# SYZYGY_IO_PORTS.net
KiCad netlist of a schematic drawn in Altium Designer
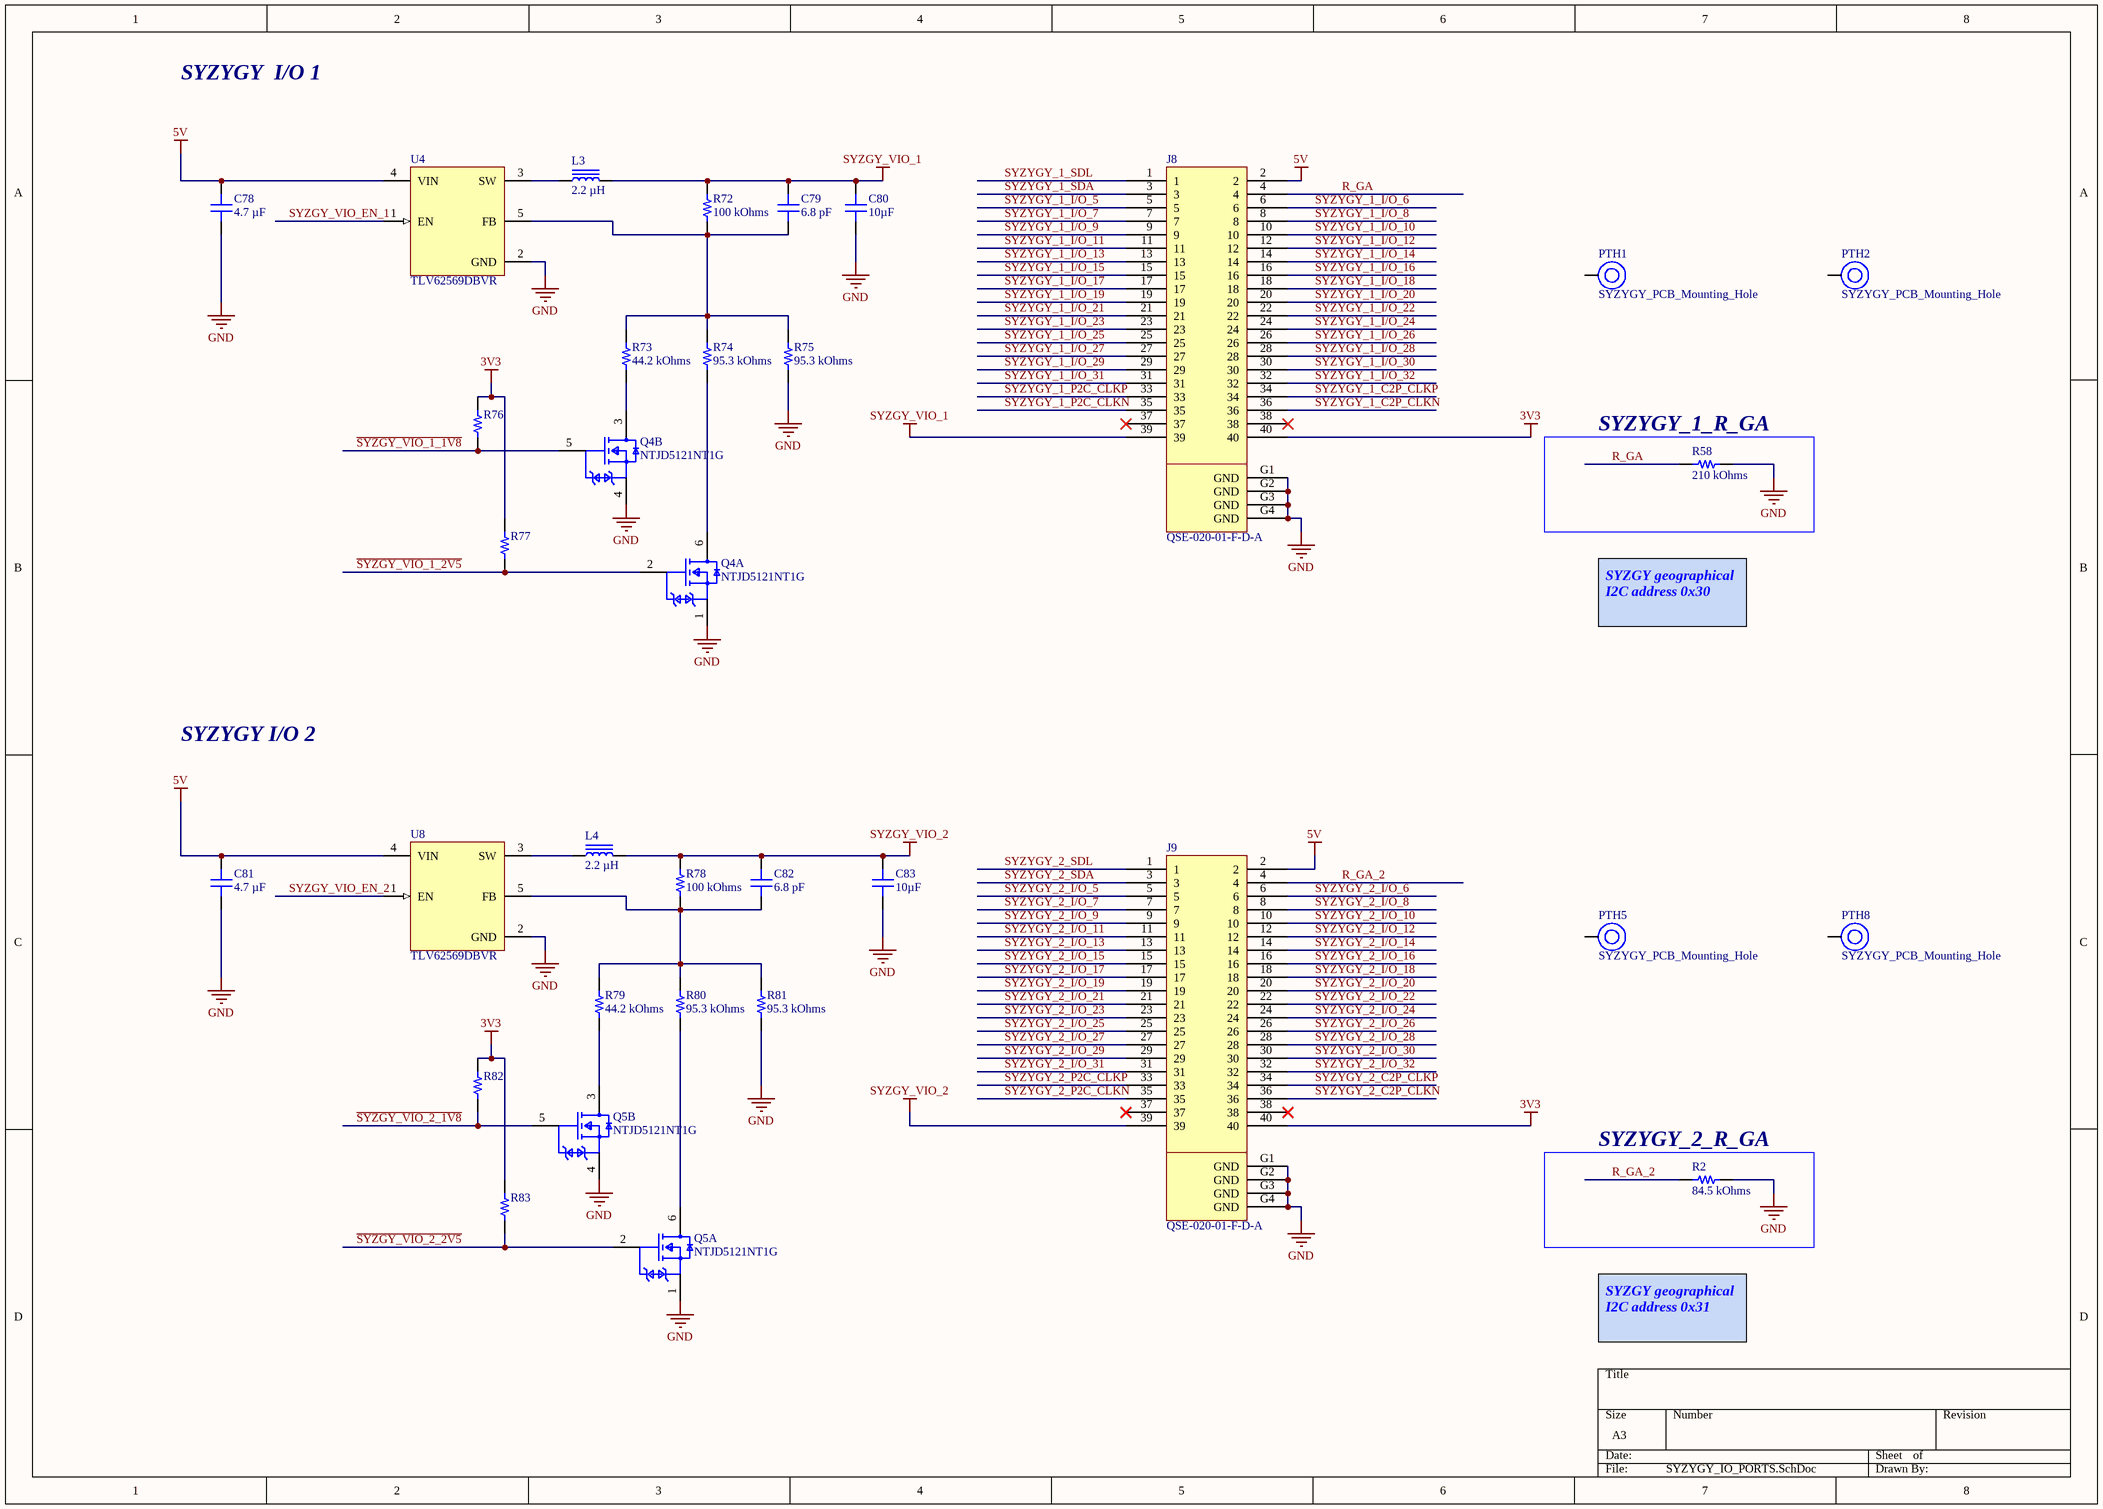
[diagram p0: SYZYGY_IO_PORTS.SchDoc]

(export (version "E")
  (design (tool "Eeschema 10.0.6"))
  (components
    (comp (ref "C78")
      (value "4.7 µF")
      (footprint "CAP 0805_2012")
      (description "CAP CER 4.7UF 25V X7R 0805")
      (fields
        (field (name "PART NUMBER") "CL21B475KAFNNNE")
        (field (name "MANUFACTURER") "Samsung Electro-Mechanics")
      )
      (libsource (lib "Celestial Altium Library - altium_library") (part "Capacitor"))
    )
    (comp (ref "C79")
      (value "6.8 pF")
      (footprint "CAP 0402_1005")
      (description "CAP CER 6.8PF 16V C0G/NP0 0402")
      (fields (field (name "PART NUMBER") "885012005024") (field (name "MANUFACTURER") "Würth Elektronik"))
      (libsource (lib "Celestial Altium Library - altium_library") (part "Capacitor"))
    )
    (comp (ref "C80")
      (value "10µF")
      (footprint "CAP 0805_2012")
      (description "CAP CER 10UF 10V X7R 0805")
      (fields (field (name "PART NUMBER") "0805ZC106MAT2A") (field (name "MANUFACTURER") "AVX Corporation"))
      (libsource (lib "Celestial Altium Library - altium_library") (part "Capacitor"))
    )
    (comp (ref "C81")
      (value "4.7 µF")
      (footprint "CAP 0805_2012")
      (description "CAP CER 4.7UF 25V X7R 0805")
      (fields
        (field (name "PART NUMBER") "CL21B475KAFNNNE")
        (field (name "MANUFACTURER") "Samsung Electro-Mechanics")
      )
      (libsource (lib "Celestial Altium Library - altium_library") (part "Capacitor"))
    )
    (comp (ref "C82")
      (value "6.8 pF")
      (footprint "CAP 0402_1005")
      (description "CAP CER 6.8PF 16V C0G/NP0 0402")
      (fields (field (name "PART NUMBER") "885012005024") (field (name "MANUFACTURER") "Würth Elektronik"))
      (libsource (lib "Celestial Altium Library - altium_library") (part "Capacitor"))
    )
    (comp (ref "C83")
      (value "10µF")
      (footprint "CAP 0805_2012")
      (description "CAP CER 10UF 10V X7R 0805")
      (fields (field (name "PART NUMBER") "0805ZC106MAT2A") (field (name "MANUFACTURER") "AVX Corporation"))
      (libsource (lib "Celestial Altium Library - altium_library") (part "Capacitor"))
    )
    (comp (ref "J8")
      (value "QSE-020-01-F-D-A")
      (footprint "Components - 26.11.22 - 19.48:QSE-020-01-F-D-A-Footprint-1")
      (description "Conn High Speed Socket Strip SKT 40 POS 0.8mm Solder ST SMD Tray")
      (libsource (lib "Components - 26.11.22 - 19.48") (part "CMP-002-00073-2"))
    )
    (comp (ref "J9")
      (value "QSE-020-01-F-D-A")
      (footprint "Components - 26.11.22 - 19.48:QSE-020-01-F-D-A-Footprint-1")
      (description "Conn High Speed Socket Strip SKT 40 POS 0.8mm Solder ST SMD Tray")
      (libsource (lib "Components - 26.11.22 - 19.48") (part "CMP-002-00073-2"))
    )
    (comp (ref "L3")
      (value "2.2 µH")
      (footprint "TDK VLS252010HBX-1")
      (description "FIXED IND 2.2UH 1.76A 120MOHM SM")
      (fields
        (field (name "PART NUMBER") "VLS252010HBX-2R2M-1")
        (field (name "MANUFACTURER") "TDK Corporation")
      )
      (libsource (lib "Celestial Altium Library - altium_library") (part "Inductor"))
    )
    (comp (ref "L4")
      (value "2.2 µH")
      (footprint "TDK VLS252010HBX-1")
      (description "FIXED IND 2.2UH 1.76A 120MOHM SM")
      (fields
        (field (name "PART NUMBER") "VLS252010HBX-2R2M-1")
        (field (name "MANUFACTURER") "TDK Corporation")
      )
      (libsource (lib "Celestial Altium Library - altium_library") (part "Inductor"))
    )
    (comp (ref "PTH1")
      (value "SYZYGY_PCB_Mounting_Hole")
      (footprint "SYZYGY_PCB_Mounting_Hole")
      (libsource (lib "T8_devkit_PCB") (part "SYZYGY_PCB_Mounting_Hole"))
    )
    (comp (ref "PTH2")
      (value "SYZYGY_PCB_Mounting_Hole")
      (footprint "SYZYGY_PCB_Mounting_Hole")
      (libsource (lib "T8_devkit_PCB") (part "SYZYGY_PCB_Mounting_Hole"))
    )
    (comp (ref "PTH5")
      (value "SYZYGY_PCB_Mounting_Hole")
      (footprint "SYZYGY_PCB_Mounting_Hole")
      (libsource (lib "T8_devkit_PCB") (part "SYZYGY_PCB_Mounting_Hole"))
    )
    (comp (ref "PTH8")
      (value "SYZYGY_PCB_Mounting_Hole")
      (footprint "SYZYGY_PCB_Mounting_Hole")
      (libsource (lib "T8_devkit_PCB") (part "SYZYGY_PCB_Mounting_Hole"))
    )
    (comp (ref "Q4")
      (value "NTJD5121NT1G")
      (footprint "FP-419B-02-MFG")
      (description "MOSFET 2N-CH 60V 0.295A SOT363")
      (libsource (lib "Components - 26.11.22 - 19.04") (part "CMP-013-00036-1"))
    )
    (comp (ref "Q5")
      (value "NTJD5121NT1G")
      (footprint "FP-419B-02-MFG")
      (description "MOSFET 2N-CH 60V 0.295A SOT363")
      (libsource (lib "Components - 26.11.22 - 19.04") (part "CMP-013-00036-1"))
    )
    (comp (ref "R2")
      (value "84.5 kOhms")
      (footprint "RES 0402_1005")
      (description "RES 84.5K OHM 1% 1/16W 0402")
      (fields (field (name "PART NUMBER") "RC0402FR-0784K5L") (field (name "MANUFACTURER") "Yageo"))
      (libsource (lib "Celestial Altium Library - altium_library") (part "Resistor"))
    )
    (comp (ref "R58")
      (value "210 kOhms")
      (footprint "RES 0402_1005")
      (description "RES 210K OHM 1% 1/16W 0402")
      (fields (field (name "PART NUMBER") "RC0402FR-07210KL") (field (name "MANUFACTURER") "Yageo"))
      (libsource (lib "Celestial Altium Library - altium_library") (part "Resistor"))
    )
    (comp (ref "R72")
      (value "100 kOhms")
      (footprint "RES 0402_1005")
      (description "RES SMD 100K OHM 1% 1/16W 0402")
      (fields (field (name "PART NUMBER") "AC0402FR-07100KL") (field (name "MANUFACTURER") "Yageo"))
      (libsource (lib "Celestial Altium Library - altium_library") (part "Resistor"))
    )
    (comp (ref "R73")
      (value "44.2 kOhms")
      (footprint "RES 0402_1005")
      (description "RES 44.2K OHM 1% 1/16W 0402")
      (fields (field (name "PART NUMBER") "RC0402FR-0744K2L") (field (name "MANUFACTURER") "Yageo"))
      (libsource (lib "Celestial Altium Library - altium_library") (part "Resistor"))
    )
    (comp (ref "R74")
      (value "95.3 kOhms")
      (footprint "RES 0402_1005")
      (description "RES 95.3K OHM 1% 1/16W 0402")
      (fields (field (name "PART NUMBER") "RC0402FR-0795K3L") (field (name "MANUFACTURER") "Yageo"))
      (libsource (lib "Celestial Altium Library - altium_library") (part "Resistor"))
    )
    (comp (ref "R75")
      (value "95.3 kOhms")
      (footprint "RES 0402_1005")
      (description "RES 95.3K OHM 1% 1/16W 0402")
      (fields (field (name "PART NUMBER") "RC0402FR-0795K3L") (field (name "MANUFACTURER") "Yageo"))
      (libsource (lib "Celestial Altium Library - altium_library") (part "Resistor"))
    )
    (comp (ref "R76")
      (value "10 kOhms")
      (footprint "RES 0201_0603")
      (description "RES 10K OHM 1% 1/20W 0201")
      (fields (field (name "PART NUMBER") "RC0201FR-0710KL") (field (name "MANUFACTURER") "Yageo"))
      (libsource (lib "Celestial Altium Library - altium_library") (part "Resistor"))
    )
    (comp (ref "R77")
      (value "10 kOhms")
      (footprint "RES 0201_0603")
      (description "RES 10K OHM 1% 1/20W 0201")
      (fields (field (name "PART NUMBER") "RC0201FR-0710KL") (field (name "MANUFACTURER") "Yageo"))
      (libsource (lib "Celestial Altium Library - altium_library") (part "Resistor"))
    )
    (comp (ref "R78")
      (value "100 kOhms")
      (footprint "RES 0402_1005")
      (description "RES SMD 100K OHM 1% 1/16W 0402")
      (fields (field (name "PART NUMBER") "AC0402FR-07100KL") (field (name "MANUFACTURER") "Yageo"))
      (libsource (lib "Celestial Altium Library - altium_library") (part "Resistor"))
    )
    (comp (ref "R79")
      (value "44.2 kOhms")
      (footprint "RES 0402_1005")
      (description "RES 44.2K OHM 1% 1/16W 0402")
      (fields (field (name "PART NUMBER") "RC0402FR-0744K2L") (field (name "MANUFACTURER") "Yageo"))
      (libsource (lib "Celestial Altium Library - altium_library") (part "Resistor"))
    )
    (comp (ref "R80")
      (value "95.3 kOhms")
      (footprint "RES 0402_1005")
      (description "RES 95.3K OHM 1% 1/16W 0402")
      (fields (field (name "PART NUMBER") "RC0402FR-0795K3L") (field (name "MANUFACTURER") "Yageo"))
      (libsource (lib "Celestial Altium Library - altium_library") (part "Resistor"))
    )
    (comp (ref "R81")
      (value "95.3 kOhms")
      (footprint "RES 0402_1005")
      (description "RES 95.3K OHM 1% 1/16W 0402")
      (fields (field (name "PART NUMBER") "RC0402FR-0795K3L") (field (name "MANUFACTURER") "Yageo"))
      (libsource (lib "Celestial Altium Library - altium_library") (part "Resistor"))
    )
    (comp (ref "R82")
      (value "10 kOhms")
      (footprint "RES 0201_0603")
      (description "RES 10K OHM 1% 1/20W 0201")
      (fields (field (name "PART NUMBER") "RC0201FR-0710KL") (field (name "MANUFACTURER") "Yageo"))
      (libsource (lib "Celestial Altium Library - altium_library") (part "Resistor"))
    )
    (comp (ref "R83")
      (value "10 kOhms")
      (footprint "RES 0201_0603")
      (description "RES 10K OHM 1% 1/20W 0201")
      (fields (field (name "PART NUMBER") "RC0201FR-0710KL") (field (name "MANUFACTURER") "Yageo"))
      (libsource (lib "Celestial Altium Library - altium_library") (part "Resistor"))
    )
    (comp (ref "U4")
      (value "TLV62569DBVR")
      (footprint "FP-DBV0005A-IPC_C")
      (description "Conv DC-DC 2.5V to 5.5V Synchronous Step Down Single-Out 0.6V to 5.5V 2A 5-Pin SOT-23 T/R")
      (libsource (lib "Components - 26.11.22 - 18.56") (part "CMP-019-00054-4"))
    )
    (comp (ref "U8")
      (value "TLV62569DBVR")
      (footprint "FP-DBV0005A-IPC_C")
      (description "Conv DC-DC 2.5V to 5.5V Synchronous Step Down Single-Out 0.6V to 5.5V 2A 5-Pin SOT-23 T/R")
      (libsource (lib "Components - 26.11.22 - 18.56") (part "CMP-019-00054-4"))
    )
  )
  (nets
    (net (code "1") (name "/R_GA") (class "Default")
      (node (ref "J8") (pin "4") (pinfunction "4_4") (pintype "passive"))
      (node (ref "R58") (pin "1") (pinfunction "1_1") (pintype "passive"))
    )
    (net (code "2") (name "/R_GA_2") (class "Default")
      (node (ref "J9") (pin "4") (pinfunction "4_4") (pintype "passive"))
      (node (ref "R2") (pin "1") (pinfunction "1_1") (pintype "passive"))
    )
    (net (code "3") (name "/SYZGY_VIO_EN_1") (class "Default")
      (node (ref "U4") (pin "1") (pinfunction "EN_1") (pintype "input"))
    )
    (net (code "4") (name "/SYZGY_VIO_EN_2") (class "Default")
      (node (ref "U8") (pin "1") (pinfunction "EN_1") (pintype "input"))
    )
    (net (code "5") (name "/SYZYGY_1_C2P_CLKN") (class "Default")
      (node (ref "J8") (pin "36") (pinfunction "36_36") (pintype "passive"))
    )
    (net (code "6") (name "/SYZYGY_1_C2P_CLKP") (class "Default")
      (node (ref "J8") (pin "34") (pinfunction "34_34") (pintype "passive"))
    )
    (net (code "7") (name "/SYZYGY_1_I{slash}O_5") (class "Default")
      (node (ref "J8") (pin "5") (pinfunction "5_5") (pintype "passive"))
    )
    (net (code "8") (name "/SYZYGY_1_I{slash}O_6") (class "Default")
      (node (ref "J8") (pin "6") (pinfunction "6_6") (pintype "passive"))
    )
    (net (code "9") (name "/SYZYGY_1_I{slash}O_7") (class "Default")
      (node (ref "J8") (pin "7") (pinfunction "7_7") (pintype "passive"))
    )
    (net (code "10") (name "/SYZYGY_1_I{slash}O_8") (class "Default")
      (node (ref "J8") (pin "8") (pinfunction "8_8") (pintype "passive"))
    )
    (net (code "11") (name "/SYZYGY_1_I{slash}O_9") (class "Default")
      (node (ref "J8") (pin "9") (pinfunction "9_9") (pintype "passive"))
    )
    (net (code "12") (name "/SYZYGY_1_I{slash}O_10") (class "Default")
      (node (ref "J8") (pin "10") (pinfunction "10_10") (pintype "passive"))
    )
    (net (code "13") (name "/SYZYGY_1_I{slash}O_11") (class "Default")
      (node (ref "J8") (pin "11") (pinfunction "11_11") (pintype "passive"))
    )
    (net (code "14") (name "/SYZYGY_1_I{slash}O_12") (class "Default")
      (node (ref "J8") (pin "12") (pinfunction "12_12") (pintype "passive"))
    )
    (net (code "15") (name "/SYZYGY_1_I{slash}O_13") (class "Default")
      (node (ref "J8") (pin "13") (pinfunction "13_13") (pintype "passive"))
    )
    (net (code "16") (name "/SYZYGY_1_I{slash}O_14") (class "Default")
      (node (ref "J8") (pin "14") (pinfunction "14_14") (pintype "passive"))
    )
    (net (code "17") (name "/SYZYGY_1_I{slash}O_15") (class "Default")
      (node (ref "J8") (pin "15") (pinfunction "15_15") (pintype "passive"))
    )
    (net (code "18") (name "/SYZYGY_1_I{slash}O_16") (class "Default")
      (node (ref "J8") (pin "16") (pinfunction "16_16") (pintype "passive"))
    )
    (net (code "19") (name "/SYZYGY_1_I{slash}O_17") (class "Default")
      (node (ref "J8") (pin "17") (pinfunction "17_17") (pintype "passive"))
    )
    (net (code "20") (name "/SYZYGY_1_I{slash}O_18") (class "Default")
      (node (ref "J8") (pin "18") (pinfunction "18_18") (pintype "passive"))
    )
    (net (code "21") (name "/SYZYGY_1_I{slash}O_19") (class "Default")
      (node (ref "J8") (pin "19") (pinfunction "19_19") (pintype "passive"))
    )
    (net (code "22") (name "/SYZYGY_1_I{slash}O_20") (class "Default")
      (node (ref "J8") (pin "20") (pinfunction "20_20") (pintype "passive"))
    )
    (net (code "23") (name "/SYZYGY_1_I{slash}O_21") (class "Default")
      (node (ref "J8") (pin "21") (pinfunction "21_21") (pintype "passive"))
    )
    (net (code "24") (name "/SYZYGY_1_I{slash}O_22") (class "Default")
      (node (ref "J8") (pin "22") (pinfunction "22_22") (pintype "passive"))
    )
    (net (code "25") (name "/SYZYGY_1_I{slash}O_23") (class "Default")
      (node (ref "J8") (pin "23") (pinfunction "23_23") (pintype "passive"))
    )
    (net (code "26") (name "/SYZYGY_1_I{slash}O_24") (class "Default")
      (node (ref "J8") (pin "24") (pinfunction "24_24") (pintype "passive"))
    )
    (net (code "27") (name "/SYZYGY_1_I{slash}O_25") (class "Default")
      (node (ref "J8") (pin "25") (pinfunction "25_25") (pintype "passive"))
    )
    (net (code "28") (name "/SYZYGY_1_I{slash}O_26") (class "Default")
      (node (ref "J8") (pin "26") (pinfunction "26_26") (pintype "passive"))
    )
    (net (code "29") (name "/SYZYGY_1_I{slash}O_27") (class "Default")
      (node (ref "J8") (pin "27") (pinfunction "27_27") (pintype "passive"))
    )
    (net (code "30") (name "/SYZYGY_1_I{slash}O_28") (class "Default")
      (node (ref "J8") (pin "28") (pinfunction "28_28") (pintype "passive"))
    )
    (net (code "31") (name "/SYZYGY_1_I{slash}O_29") (class "Default")
      (node (ref "J8") (pin "29") (pinfunction "29_29") (pintype "passive"))
    )
    (net (code "32") (name "/SYZYGY_1_I{slash}O_30") (class "Default")
      (node (ref "J8") (pin "30") (pinfunction "30_30") (pintype "passive"))
    )
    (net (code "33") (name "/SYZYGY_1_I{slash}O_31") (class "Default")
      (node (ref "J8") (pin "31") (pinfunction "31_31") (pintype "passive"))
    )
    (net (code "34") (name "/SYZYGY_1_I{slash}O_32") (class "Default")
      (node (ref "J8") (pin "32") (pinfunction "32_32") (pintype "passive"))
    )
    (net (code "35") (name "/SYZYGY_1_P2C_CLKN") (class "Default")
      (node (ref "J8") (pin "35") (pinfunction "35_35") (pintype "passive"))
    )
    (net (code "36") (name "/SYZYGY_1_P2C_CLKP") (class "Default")
      (node (ref "J8") (pin "33") (pinfunction "33_33") (pintype "passive"))
    )
    (net (code "37") (name "/SYZYGY_1_SDA") (class "Default")
      (node (ref "J8") (pin "3") (pinfunction "3_3") (pintype "passive"))
    )
    (net (code "38") (name "/SYZYGY_1_SDL") (class "Default")
      (node (ref "J8") (pin "1") (pinfunction "1_1") (pintype "passive"))
    )
    (net (code "39") (name "/SYZYGY_2_C2P_CLKN") (class "Default")
      (node (ref "J9") (pin "36") (pinfunction "36_36") (pintype "passive"))
    )
    (net (code "40") (name "/SYZYGY_2_C2P_CLKP") (class "Default")
      (node (ref "J9") (pin "34") (pinfunction "34_34") (pintype "passive"))
    )
    (net (code "41") (name "/SYZYGY_2_I{slash}O_5") (class "Default")
      (node (ref "J9") (pin "5") (pinfunction "5_5") (pintype "passive"))
    )
    (net (code "42") (name "/SYZYGY_2_I{slash}O_6") (class "Default")
      (node (ref "J9") (pin "6") (pinfunction "6_6") (pintype "passive"))
    )
    (net (code "43") (name "/SYZYGY_2_I{slash}O_7") (class "Default")
      (node (ref "J9") (pin "7") (pinfunction "7_7") (pintype "passive"))
    )
    (net (code "44") (name "/SYZYGY_2_I{slash}O_8") (class "Default")
      (node (ref "J9") (pin "8") (pinfunction "8_8") (pintype "passive"))
    )
    (net (code "45") (name "/SYZYGY_2_I{slash}O_9") (class "Default")
      (node (ref "J9") (pin "9") (pinfunction "9_9") (pintype "passive"))
    )
    (net (code "46") (name "/SYZYGY_2_I{slash}O_10") (class "Default")
      (node (ref "J9") (pin "10") (pinfunction "10_10") (pintype "passive"))
    )
    (net (code "47") (name "/SYZYGY_2_I{slash}O_11") (class "Default")
      (node (ref "J9") (pin "11") (pinfunction "11_11") (pintype "passive"))
    )
    (net (code "48") (name "/SYZYGY_2_I{slash}O_12") (class "Default")
      (node (ref "J9") (pin "12") (pinfunction "12_12") (pintype "passive"))
    )
    (net (code "49") (name "/SYZYGY_2_I{slash}O_13") (class "Default")
      (node (ref "J9") (pin "13") (pinfunction "13_13") (pintype "passive"))
    )
    (net (code "50") (name "/SYZYGY_2_I{slash}O_14") (class "Default")
      (node (ref "J9") (pin "14") (pinfunction "14_14") (pintype "passive"))
    )
    (net (code "51") (name "/SYZYGY_2_I{slash}O_15") (class "Default")
      (node (ref "J9") (pin "15") (pinfunction "15_15") (pintype "passive"))
    )
    (net (code "52") (name "/SYZYGY_2_I{slash}O_16") (class "Default")
      (node (ref "J9") (pin "16") (pinfunction "16_16") (pintype "passive"))
    )
    (net (code "53") (name "/SYZYGY_2_I{slash}O_17") (class "Default")
      (node (ref "J9") (pin "17") (pinfunction "17_17") (pintype "passive"))
    )
    (net (code "54") (name "/SYZYGY_2_I{slash}O_18") (class "Default")
      (node (ref "J9") (pin "18") (pinfunction "18_18") (pintype "passive"))
    )
    (net (code "55") (name "/SYZYGY_2_I{slash}O_19") (class "Default")
      (node (ref "J9") (pin "19") (pinfunction "19_19") (pintype "passive"))
    )
    (net (code "56") (name "/SYZYGY_2_I{slash}O_20") (class "Default")
      (node (ref "J9") (pin "20") (pinfunction "20_20") (pintype "passive"))
    )
    (net (code "57") (name "/SYZYGY_2_I{slash}O_21") (class "Default")
      (node (ref "J9") (pin "21") (pinfunction "21_21") (pintype "passive"))
    )
    (net (code "58") (name "/SYZYGY_2_I{slash}O_22") (class "Default")
      (node (ref "J9") (pin "22") (pinfunction "22_22") (pintype "passive"))
    )
    (net (code "59") (name "/SYZYGY_2_I{slash}O_23") (class "Default")
      (node (ref "J9") (pin "23") (pinfunction "23_23") (pintype "passive"))
    )
    (net (code "60") (name "/SYZYGY_2_I{slash}O_24") (class "Default")
      (node (ref "J9") (pin "24") (pinfunction "24_24") (pintype "passive"))
    )
    (net (code "61") (name "/SYZYGY_2_I{slash}O_25") (class "Default")
      (node (ref "J9") (pin "25") (pinfunction "25_25") (pintype "passive"))
    )
    (net (code "62") (name "/SYZYGY_2_I{slash}O_26") (class "Default")
      (node (ref "J9") (pin "26") (pinfunction "26_26") (pintype "passive"))
    )
    (net (code "63") (name "/SYZYGY_2_I{slash}O_27") (class "Default")
      (node (ref "J9") (pin "27") (pinfunction "27_27") (pintype "passive"))
    )
    (net (code "64") (name "/SYZYGY_2_I{slash}O_28") (class "Default")
      (node (ref "J9") (pin "28") (pinfunction "28_28") (pintype "passive"))
    )
    (net (code "65") (name "/SYZYGY_2_I{slash}O_29") (class "Default")
      (node (ref "J9") (pin "29") (pinfunction "29_29") (pintype "passive"))
    )
    (net (code "66") (name "/SYZYGY_2_I{slash}O_30") (class "Default")
      (node (ref "J9") (pin "30") (pinfunction "30_30") (pintype "passive"))
    )
    (net (code "67") (name "/SYZYGY_2_I{slash}O_31") (class "Default")
      (node (ref "J9") (pin "31") (pinfunction "31_31") (pintype "passive"))
    )
    (net (code "68") (name "/SYZYGY_2_I{slash}O_32") (class "Default")
      (node (ref "J9") (pin "32") (pinfunction "32_32") (pintype "passive"))
    )
    (net (code "69") (name "/SYZYGY_2_P2C_CLKN") (class "Default")
      (node (ref "J9") (pin "35") (pinfunction "35_35") (pintype "passive"))
    )
    (net (code "70") (name "/SYZYGY_2_P2C_CLKP") (class "Default")
      (node (ref "J9") (pin "33") (pinfunction "33_33") (pintype "passive"))
    )
    (net (code "71") (name "/SYZYGY_2_SDA") (class "Default")
      (node (ref "J9") (pin "3") (pinfunction "3_3") (pintype "passive"))
    )
    (net (code "72") (name "/SYZYGY_2_SDL") (class "Default")
      (node (ref "J9") (pin "1") (pinfunction "1_1") (pintype "passive"))
    )
    (net (code "73") (name "/~{SYZGY_VIO_1_1V8}") (class "Default")
      (node (ref "Q4") (pin "5") (pinfunction "G2_5") (pintype "passive"))
      (node (ref "R76") (pin "1") (pinfunction "1_1") (pintype "passive"))
    )
    (net (code "74") (name "/~{SYZGY_VIO_1_2V5}") (class "Default")
      (node (ref "Q4") (pin "2") (pinfunction "G1_2") (pintype "passive"))
      (node (ref "R77") (pin "1") (pinfunction "1_1") (pintype "passive"))
    )
    (net (code "75") (name "/~{SYZGY_VIO_2_1V8}") (class "Default")
      (node (ref "Q5") (pin "5") (pinfunction "G2_5") (pintype "passive"))
      (node (ref "R82") (pin "1") (pinfunction "1_1") (pintype "passive"))
    )
    (net (code "76") (name "/~{SYZGY_VIO_2_2V5}") (class "Default")
      (node (ref "Q5") (pin "2") (pinfunction "G1_2") (pintype "passive"))
      (node (ref "R83") (pin "1") (pinfunction "1_1") (pintype "passive"))
    )
    (net (code "77") (name "3V3") (class "Default")
      (node (ref "J8") (pin "40") (pinfunction "40_40") (pintype "passive"))
      (node (ref "J9") (pin "40") (pinfunction "40_40") (pintype "passive"))
      (node (ref "R76") (pin "2") (pinfunction "2_2") (pintype "passive"))
      (node (ref "R77") (pin "2") (pinfunction "2_2") (pintype "passive"))
      (node (ref "R82") (pin "2") (pinfunction "2_2") (pintype "passive"))
      (node (ref "R83") (pin "2") (pinfunction "2_2") (pintype "passive"))
    )
    (net (code "78") (name "5V") (class "Default")
      (node (ref "C78") (pin "2") (pinfunction "2_2") (pintype "passive"))
      (node (ref "C81") (pin "2") (pinfunction "2_2") (pintype "passive"))
      (node (ref "J8") (pin "2") (pinfunction "2_2") (pintype "passive"))
      (node (ref "J9") (pin "2") (pinfunction "2_2") (pintype "passive"))
      (node (ref "U4") (pin "4") (pinfunction "VIN_4") (pintype "power_in"))
      (node (ref "U8") (pin "4") (pinfunction "VIN_4") (pintype "power_in"))
    )
    (net (code "79") (name "GND") (class "Default")
      (node (ref "C78") (pin "1") (pinfunction "1_1") (pintype "passive"))
      (node (ref "C80") (pin "1") (pinfunction "1_1") (pintype "passive"))
      (node (ref "C81") (pin "1") (pinfunction "1_1") (pintype "passive"))
      (node (ref "C83") (pin "1") (pinfunction "1_1") (pintype "passive"))
      (node (ref "J8") (pin "G1") (pinfunction "GND_G1") (pintype "power_in"))
      (node (ref "J8") (pin "G2") (pinfunction "GND_G2") (pintype "power_in"))
      (node (ref "J8") (pin "G3") (pinfunction "GND_G3") (pintype "power_in"))
      (node (ref "J8") (pin "G4") (pinfunction "GND_G4") (pintype "power_in"))
      (node (ref "J9") (pin "G1") (pinfunction "GND_G1") (pintype "power_in"))
      (node (ref "J9") (pin "G2") (pinfunction "GND_G2") (pintype "power_in"))
      (node (ref "J9") (pin "G3") (pinfunction "GND_G3") (pintype "power_in"))
      (node (ref "J9") (pin "G4") (pinfunction "GND_G4") (pintype "power_in"))
      (node (ref "Q4") (pin "1") (pinfunction "S1_1") (pintype "passive"))
      (node (ref "Q4") (pin "4") (pinfunction "S2_4") (pintype "passive"))
      (node (ref "Q5") (pin "1") (pinfunction "S1_1") (pintype "passive"))
      (node (ref "Q5") (pin "4") (pinfunction "S2_4") (pintype "passive"))
      (node (ref "R2") (pin "2") (pinfunction "2_2") (pintype "passive"))
      (node (ref "R58") (pin "2") (pinfunction "2_2") (pintype "passive"))
      (node (ref "R75") (pin "1") (pinfunction "1_1") (pintype "passive"))
      (node (ref "R81") (pin "1") (pinfunction "1_1") (pintype "passive"))
      (node (ref "U4") (pin "2") (pinfunction "GND_2") (pintype "power_in"))
      (node (ref "U8") (pin "2") (pinfunction "GND_2") (pintype "power_in"))
    )
    (net (code "80") (name "Net-(Q4A-D1)") (class "Default")
      (node (ref "Q4") (pin "6") (pinfunction "D1_6") (pintype "passive"))
      (node (ref "R74") (pin "1") (pinfunction "1_1") (pintype "passive"))
    )
    (net (code "81") (name "Net-(Q4B-D2)") (class "Default")
      (node (ref "Q4") (pin "3") (pinfunction "D2_3") (pintype "passive"))
      (node (ref "R73") (pin "1") (pinfunction "1_1") (pintype "passive"))
    )
    (net (code "82") (name "Net-(Q5A-D1)") (class "Default")
      (node (ref "Q5") (pin "6") (pinfunction "D1_6") (pintype "passive"))
      (node (ref "R80") (pin "1") (pinfunction "1_1") (pintype "passive"))
    )
    (net (code "83") (name "Net-(Q5B-D2)") (class "Default")
      (node (ref "Q5") (pin "3") (pinfunction "D2_3") (pintype "passive"))
      (node (ref "R79") (pin "1") (pinfunction "1_1") (pintype "passive"))
    )
    (net (code "84") (name "Net-(U4-FB)") (class "Default")
      (node (ref "C79") (pin "1") (pinfunction "1_1") (pintype "passive"))
      (node (ref "R72") (pin "1") (pinfunction "1_1") (pintype "passive"))
      (node (ref "R73") (pin "2") (pinfunction "2_2") (pintype "passive"))
      (node (ref "R74") (pin "2") (pinfunction "2_2") (pintype "passive"))
      (node (ref "R75") (pin "2") (pinfunction "2_2") (pintype "passive"))
      (node (ref "U4") (pin "5") (pinfunction "FB_5") (pintype "passive"))
    )
    (net (code "85") (name "Net-(U4-SW)") (class "Default")
      (node (ref "L3") (pin "1") (pinfunction "1_1") (pintype "passive"))
      (node (ref "U4") (pin "3") (pinfunction "SW_3") (pintype "power_in"))
    )
    (net (code "86") (name "Net-(U8-FB)") (class "Default")
      (node (ref "C82") (pin "1") (pinfunction "1_1") (pintype "passive"))
      (node (ref "R78") (pin "1") (pinfunction "1_1") (pintype "passive"))
      (node (ref "R79") (pin "2") (pinfunction "2_2") (pintype "passive"))
      (node (ref "R80") (pin "2") (pinfunction "2_2") (pintype "passive"))
      (node (ref "R81") (pin "2") (pinfunction "2_2") (pintype "passive"))
      (node (ref "U8") (pin "5") (pinfunction "FB_5") (pintype "passive"))
    )
    (net (code "87") (name "Net-(U8-SW)") (class "Default")
      (node (ref "L4") (pin "1") (pinfunction "1_1") (pintype "passive"))
      (node (ref "U8") (pin "3") (pinfunction "SW_3") (pintype "power_in"))
    )
    (net (code "88") (name "SYZGY_VIO_1") (class "Default")
      (node (ref "C79") (pin "2") (pinfunction "2_2") (pintype "passive"))
      (node (ref "C80") (pin "2") (pinfunction "2_2") (pintype "passive"))
      (node (ref "J8") (pin "39") (pinfunction "39_39") (pintype "passive"))
      (node (ref "L3") (pin "2") (pinfunction "2_2") (pintype "passive"))
      (node (ref "R72") (pin "2") (pinfunction "2_2") (pintype "passive"))
    )
    (net (code "89") (name "SYZGY_VIO_2") (class "Default")
      (node (ref "C82") (pin "2") (pinfunction "2_2") (pintype "passive"))
      (node (ref "C83") (pin "2") (pinfunction "2_2") (pintype "passive"))
      (node (ref "J9") (pin "39") (pinfunction "39_39") (pintype "passive"))
      (node (ref "L4") (pin "2") (pinfunction "2_2") (pintype "passive"))
      (node (ref "R78") (pin "2") (pinfunction "2_2") (pintype "passive"))
    )
    (net (code "90") (name "unconnected-(J8-Pad37)") (class "Default")
      (node (ref "J8") (pin "37") (pinfunction "37_37") (pintype "passive+no_connect"))
    )
    (net (code "91") (name "unconnected-(J8-Pad38)") (class "Default")
      (node (ref "J8") (pin "38") (pinfunction "38_38") (pintype "passive+no_connect"))
    )
    (net (code "92") (name "unconnected-(J9-Pad37)") (class "Default")
      (node (ref "J9") (pin "37") (pinfunction "37_37") (pintype "passive+no_connect"))
    )
    (net (code "93") (name "unconnected-(J9-Pad38)") (class "Default")
      (node (ref "J9") (pin "38") (pinfunction "38_38") (pintype "passive+no_connect"))
    )
    (net (code "94") (name "unconnected-(PTH1-Pad1)") (class "Default")
      (node (ref "PTH1") (pin "1") (pinfunction "1_1") (pintype "passive"))
    )
    (net (code "95") (name "unconnected-(PTH2-Pad1)") (class "Default")
      (node (ref "PTH2") (pin "1") (pinfunction "1_1") (pintype "passive"))
    )
    (net (code "96") (name "unconnected-(PTH5-Pad1)") (class "Default")
      (node (ref "PTH5") (pin "1") (pinfunction "1_1") (pintype "passive"))
    )
    (net (code "97") (name "unconnected-(PTH8-Pad1)") (class "Default")
      (node (ref "PTH8") (pin "1") (pinfunction "1_1") (pintype "passive"))
    )
  )
)
